# CPU.net
KiCad netlist of a schematic drawn in Altium Designer
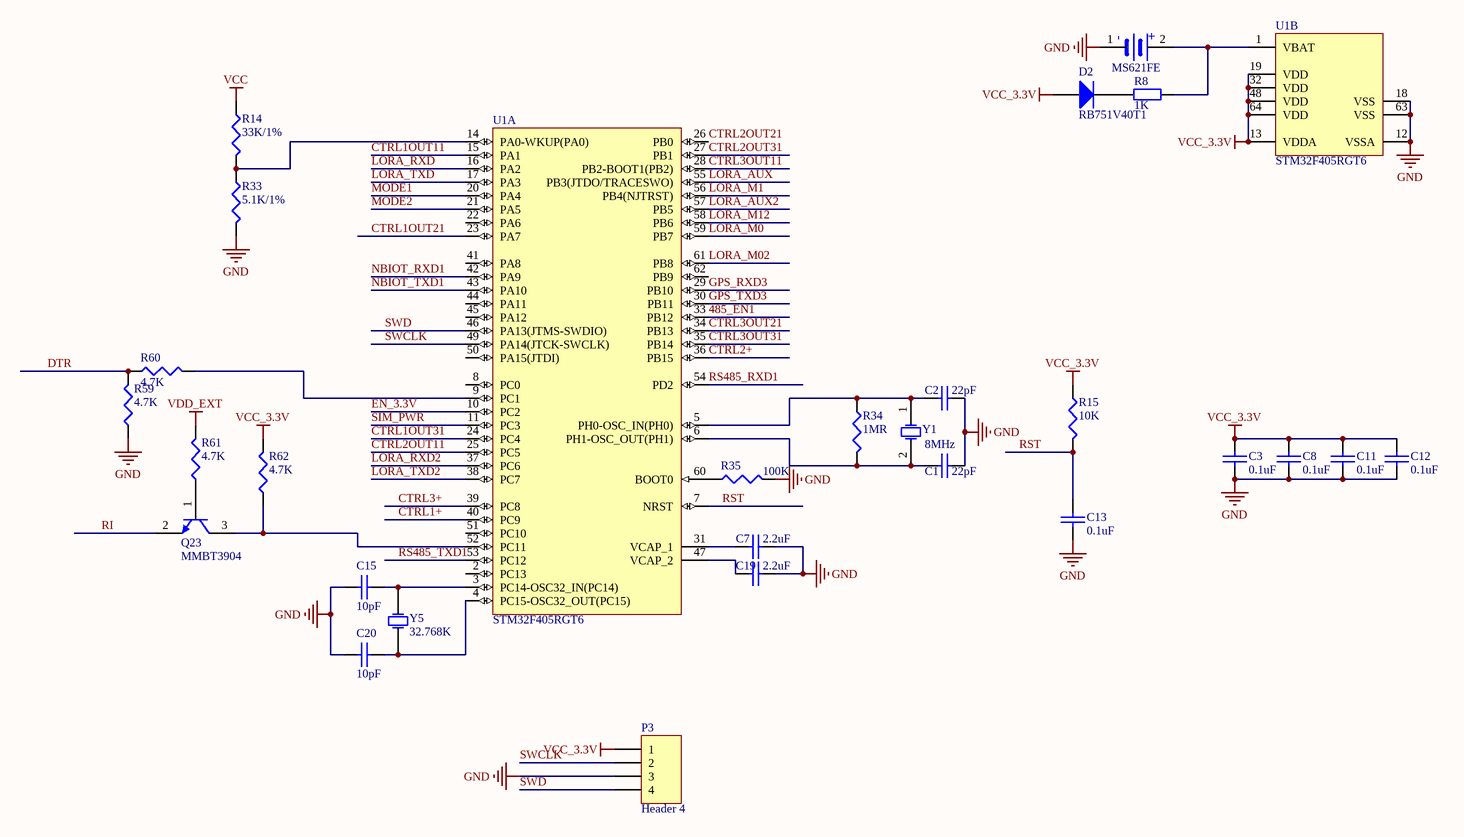
[diagram p0: CPU.SchDoc]

(export (version "E")
  (design (tool "Eeschema 10.0.6"))
  (components
    (comp (ref "C1")
      (value "22pF")
      (footprint "0603c")
      (description "Capacitor")
      (libsource (lib "SM") (part "CAP"))
    )
    (comp (ref "C2")
      (value "22pF")
      (footprint "0603c")
      (description "Capacitor")
      (libsource (lib "SM") (part "CAP"))
    )
    (comp (ref "C3")
      (value "0.1uF")
      (footprint "0603c")
      (description "Capacitor")
      (libsource (lib "SM") (part "CAP"))
    )
    (comp (ref "C7")
      (value "2.2uF")
      (footprint "0603c")
      (description "Capacitor")
      (libsource (lib "SM") (part "CAP"))
    )
    (comp (ref "C8")
      (value "0.1uF")
      (footprint "0603c")
      (description "Capacitor")
      (libsource (lib "SM") (part "CAP"))
    )
    (comp (ref "C11")
      (value "0.1uF")
      (footprint "0603c")
      (description "Capacitor")
      (libsource (lib "SM") (part "CAP"))
    )
    (comp (ref "C12")
      (value "0.1uF")
      (footprint "0603c")
      (description "Capacitor")
      (libsource (lib "SM") (part "CAP"))
    )
    (comp (ref "C13")
      (value "0.1uF")
      (footprint "0603c")
      (description "Capacitor")
      (libsource (lib "SM") (part "CAP"))
    )
    (comp (ref "C15")
      (value "10pF")
      (footprint "0603c")
      (description "Capacitor")
      (libsource (lib "SM") (part "CAP"))
    )
    (comp (ref "C19")
      (value "2.2uF")
      (footprint "0603c")
      (description "Capacitor")
      (libsource (lib "SM") (part "CAP"))
    )
    (comp (ref "C20")
      (value "10pF")
      (footprint "0603c")
      (description "Capacitor")
      (libsource (lib "SM") (part "CAP"))
    )
    (comp (ref "D2")
      (value "RB751V40T1")
      (footprint "SOD323")
      (description "Default Diode")
      (fields (field (name "PUBLISHER") "Altium Limited"))
      (libsource (lib "Miscellaneous Devices") (part "Diode"))
    )
    (comp (ref "MS621FE")
      (value "SBatery")
      (footprint "MS621FE")
      (libsource (lib "Myself_1") (part "SBatery"))
    )
    (comp (ref "P3")
      (value "Header 4")
      (footprint "HDR1X4")
      (description "Header, 4-Pin")
      (fields (field (name "PUBLISHER") "Altium Limited"))
      (libsource (lib "Miscellaneous Connectors") (part "Header 4"))
    )
    (comp (ref "Q23") (value "MMBT3904") (footprint "SOT23-3") (libsource (lib "Schlib1") (part "NPN")))
    (comp (ref "R8")
      (value "1K")
      (footprint "0603R")
      (description "Resistor")
      (fields (field (name "PUBLISHER") "Altium Limited"))
      (libsource (lib "Miscellaneous Devices") (part "Res2"))
    )
    (comp (ref "R14")
      (value "33K/1%")
      (footprint "0603R")
      (description "Resistor")
      (fields (field (name "PUBLISHER") "Altium Limited"))
      (libsource (lib "SM") (part "Res3"))
    )
    (comp (ref "R15")
      (value "10K")
      (footprint "0603R")
      (description "Resistor")
      (fields (field (name "PUBLISHER") "Altium Limited"))
      (libsource (lib "SM") (part "Res3"))
    )
    (comp (ref "R33")
      (value "5.1K/1%")
      (footprint "0603R")
      (description "Resistor")
      (fields (field (name "PUBLISHER") "Altium Limited"))
      (libsource (lib "SM") (part "Res3"))
    )
    (comp (ref "R34")
      (value "1MR")
      (footprint "0603R")
      (description "Resistor")
      (fields (field (name "PUBLISHER") "Altium Limited"))
      (libsource (lib "SM") (part "Res3"))
    )
    (comp (ref "R35")
      (value "100K")
      (footprint "0603R")
      (description "Resistor")
      (fields (field (name "PUBLISHER") "Altium Limited"))
      (libsource (lib "SM") (part "Res3"))
    )
    (comp (ref "R59")
      (value "4.7K")
      (footprint "0603R")
      (libsource (lib "ZWLIntegrated_Library") (part "RES1"))
    )
    (comp (ref "R60")
      (value "4.7K")
      (footprint "0603R")
      (libsource (lib "ZWLIntegrated_Library") (part "RES1"))
    )
    (comp (ref "R61")
      (value "4.7K")
      (footprint "0603R")
      (libsource (lib "ZWLIntegrated_Library") (part "RES1"))
    )
    (comp (ref "R62")
      (value "4.7K")
      (footprint "0603R")
      (libsource (lib "ZWLIntegrated_Library") (part "RES1"))
    )
    (comp (ref "U1")
      (value "STM32F405RGT6")
      (footprint "STM-LQFP64_N")
      (fields (field (name "MANUFACTURER") "STMicroelectronics"))
      (libsource (lib "STMicroelectronics STM32 F4") (part "STM32F405RGT6"))
    )
    (comp (ref "Y1")
      (value "8MHz")
      (footprint "CRAY_5032")
      (description "Crystal Oscillator")
      (fields (field (name "PUBLISHER") "Altium Limited"))
      (libsource (lib "Miscellaneous Devices") (part "XTAL"))
    )
    (comp (ref "Y5")
      (value "32.768K")
      (footprint "32.768K")
      (description "Crystal Oscillator")
      (fields (field (name "PUBLISHER") "Altium Limited"))
      (libsource (lib "") (part "XTAL_1"))
    )
  )
  (nets
    (net (code "1") (name "/485_EN1") (class "Default")
      (node (ref "U1") (pin "33") (pinfunction "PB12_33") (pintype "bidirectional"))
    )
    (net (code "2") (name "/CTRL1+") (class "Default")
      (node (ref "U1") (pin "40") (pinfunction "PC9_40") (pintype "bidirectional"))
    )
    (net (code "3") (name "/CTRL1OUT11") (class "Default")
      (node (ref "U1") (pin "15") (pinfunction "PA1_15") (pintype "bidirectional"))
    )
    (net (code "4") (name "/CTRL1OUT21") (class "Default")
      (node (ref "U1") (pin "23") (pinfunction "PA7_23") (pintype "bidirectional"))
    )
    (net (code "5") (name "/CTRL1OUT31") (class "Default")
      (node (ref "U1") (pin "24") (pinfunction "PC4_24") (pintype "bidirectional"))
    )
    (net (code "6") (name "/CTRL2+") (class "Default")
      (node (ref "U1") (pin "36") (pinfunction "PB15_36") (pintype "bidirectional"))
    )
    (net (code "7") (name "/CTRL2OUT11") (class "Default")
      (node (ref "U1") (pin "25") (pinfunction "PC5_25") (pintype "bidirectional"))
    )
    (net (code "8") (name "/CTRL2OUT21") (class "Default")
      (node (ref "U1") (pin "26") (pinfunction "PB0_26") (pintype "bidirectional"))
    )
    (net (code "9") (name "/CTRL2OUT31") (class "Default")
      (node (ref "U1") (pin "27") (pinfunction "PB1_27") (pintype "bidirectional"))
    )
    (net (code "10") (name "/CTRL3+") (class "Default")
      (node (ref "U1") (pin "39") (pinfunction "PC8_39") (pintype "bidirectional"))
    )
    (net (code "11") (name "/CTRL3OUT11") (class "Default")
      (node (ref "U1") (pin "28") (pinfunction "PB2-BOOT1(PB2)_28") (pintype "bidirectional"))
    )
    (net (code "12") (name "/CTRL3OUT21") (class "Default")
      (node (ref "U1") (pin "34") (pinfunction "PB13_34") (pintype "bidirectional"))
    )
    (net (code "13") (name "/CTRL3OUT31") (class "Default")
      (node (ref "U1") (pin "35") (pinfunction "PB14_35") (pintype "bidirectional"))
    )
    (net (code "14") (name "/DTR") (class "Default")
      (node (ref "R59") (pin "2") (pinfunction "2_2") (pintype "passive"))
      (node (ref "R60") (pin "1") (pinfunction "1_1") (pintype "passive"))
    )
    (net (code "15") (name "/EN_3.3V") (class "Default")
      (node (ref "U1") (pin "10") (pinfunction "PC2_10") (pintype "bidirectional"))
    )
    (net (code "16") (name "/GPS_RXD3") (class "Default")
      (node (ref "U1") (pin "29") (pinfunction "PB10_29") (pintype "bidirectional"))
    )
    (net (code "17") (name "/GPS_TXD3") (class "Default")
      (node (ref "U1") (pin "30") (pinfunction "PB11_30") (pintype "bidirectional"))
    )
    (net (code "18") (name "/LORA_AUX") (class "Default")
      (node (ref "U1") (pin "55") (pinfunction "PB3(JTDO/TRACESWO)_55") (pintype "bidirectional"))
    )
    (net (code "19") (name "/LORA_AUX2") (class "Default")
      (node (ref "U1") (pin "57") (pinfunction "PB5_57") (pintype "bidirectional"))
    )
    (net (code "20") (name "/LORA_M0") (class "Default")
      (node (ref "U1") (pin "59") (pinfunction "PB7_59") (pintype "bidirectional"))
    )
    (net (code "21") (name "/LORA_M1") (class "Default")
      (node (ref "U1") (pin "56") (pinfunction "PB4(NJTRST)_56") (pintype "bidirectional"))
    )
    (net (code "22") (name "/LORA_M02") (class "Default")
      (node (ref "U1") (pin "61") (pinfunction "PB8_61") (pintype "bidirectional"))
    )
    (net (code "23") (name "/LORA_M12") (class "Default")
      (node (ref "U1") (pin "58") (pinfunction "PB6_58") (pintype "bidirectional"))
    )
    (net (code "24") (name "/LORA_RXD") (class "Default")
      (node (ref "U1") (pin "16") (pinfunction "PA2_16") (pintype "bidirectional"))
    )
    (net (code "25") (name "/LORA_RXD2") (class "Default")
      (node (ref "U1") (pin "37") (pinfunction "PC6_37") (pintype "bidirectional"))
    )
    (net (code "26") (name "/LORA_TXD") (class "Default")
      (node (ref "U1") (pin "17") (pinfunction "PA3_17") (pintype "bidirectional"))
    )
    (net (code "27") (name "/LORA_TXD2") (class "Default")
      (node (ref "U1") (pin "38") (pinfunction "PC7_38") (pintype "bidirectional"))
    )
    (net (code "28") (name "/MODE1") (class "Default")
      (node (ref "U1") (pin "20") (pinfunction "PA4_20") (pintype "bidirectional"))
    )
    (net (code "29") (name "/MODE2") (class "Default")
      (node (ref "U1") (pin "21") (pinfunction "PA5_21") (pintype "bidirectional"))
    )
    (net (code "30") (name "/NBIOT_RXD1") (class "Default")
      (node (ref "U1") (pin "42") (pinfunction "PA9_42") (pintype "bidirectional"))
    )
    (net (code "31") (name "/NBIOT_TXD1") (class "Default")
      (node (ref "U1") (pin "43") (pinfunction "PA10_43") (pintype "bidirectional"))
    )
    (net (code "32") (name "/RI") (class "Default")
      (node (ref "Q23") (pin "2") (pinfunction "E_2") (pintype "passive"))
    )
    (net (code "33") (name "/RS485_RXD1") (class "Default")
      (node (ref "U1") (pin "54") (pinfunction "PD2_54") (pintype "bidirectional"))
    )
    (net (code "34") (name "/RS485_TXD1") (class "Default")
      (node (ref "U1") (pin "53") (pinfunction "PC12_53") (pintype "bidirectional"))
    )
    (net (code "35") (name "/RST") (class "Default")
      (node (ref "C13") (pin "2") (pinfunction "2_2") (pintype "passive"))
      (node (ref "R15") (pin "2") (pinfunction "2_2") (pintype "passive"))
      (node (ref "U1") (pin "7") (pinfunction "NRST_7") (pintype "bidirectional"))
    )
    (net (code "36") (name "/SIM_PWR") (class "Default")
      (node (ref "U1") (pin "11") (pinfunction "PC3_11") (pintype "bidirectional"))
    )
    (net (code "37") (name "/SWCLK") (class "Default")
      (node (ref "P3") (pin "2") (pinfunction "2_2") (pintype "passive"))
      (node (ref "U1") (pin "49") (pinfunction "PA14(JTCK-SWCLK)_49") (pintype "bidirectional"))
    )
    (net (code "38") (name "/SWD") (class "Default")
      (node (ref "P3") (pin "4") (pinfunction "4_4") (pintype "passive"))
      (node (ref "U1") (pin "46") (pinfunction "PA13(JTMS-SWDIO)_46") (pintype "bidirectional"))
    )
    (net (code "39") (name "GND") (class "Default")
      (node (ref "C1") (pin "1") (pinfunction "1_1") (pintype "passive"))
      (node (ref "C11") (pin "1") (pinfunction "1_1") (pintype "passive"))
      (node (ref "C12") (pin "1") (pinfunction "1_1") (pintype "passive"))
      (node (ref "C13") (pin "1") (pinfunction "1_1") (pintype "passive"))
      (node (ref "C15") (pin "1") (pinfunction "1_1") (pintype "passive"))
      (node (ref "C19") (pin "1") (pinfunction "1_1") (pintype "passive"))
      (node (ref "C2") (pin "1") (pinfunction "1_1") (pintype "passive"))
      (node (ref "C20") (pin "1") (pinfunction "1_1") (pintype "passive"))
      (node (ref "C3") (pin "1") (pinfunction "1_1") (pintype "passive"))
      (node (ref "C7") (pin "1") (pinfunction "1_1") (pintype "passive"))
      (node (ref "C8") (pin "1") (pinfunction "1_1") (pintype "passive"))
      (node (ref "MS621FE") (pin "1") (pinfunction "1_1") (pintype "passive"))
      (node (ref "P3") (pin "3") (pinfunction "3_3") (pintype "passive"))
      (node (ref "R33") (pin "2") (pinfunction "2_2") (pintype "passive"))
      (node (ref "R35") (pin "2") (pinfunction "2_2") (pintype "passive"))
      (node (ref "R59") (pin "1") (pinfunction "1_1") (pintype "passive"))
      (node (ref "U1") (pin "12") (pinfunction "VSSA_12") (pintype "power_in"))
      (node (ref "U1") (pin "18") (pinfunction "VSS_18") (pintype "power_in"))
      (node (ref "U1") (pin "63") (pinfunction "VSS_63") (pintype "power_in"))
    )
    (net (code "40") (name "Net-(D2-K)") (class "Default")
      (node (ref "D2") (pin "2") (pinfunction "K_2") (pintype "passive"))
      (node (ref "R8") (pin "1") (pinfunction "1_1") (pintype "passive"))
    )
    (net (code "41") (name "Net-(Q23-B)") (class "Default")
      (node (ref "Q23") (pin "1") (pinfunction "B_1") (pintype "passive"))
      (node (ref "R61") (pin "1") (pinfunction "1_1") (pintype "passive"))
    )
    (net (code "42") (name "Net-(Q23-C)") (class "Default")
      (node (ref "Q23") (pin "3") (pinfunction "C_3") (pintype "passive"))
      (node (ref "R62") (pin "1") (pinfunction "1_1") (pintype "passive"))
      (node (ref "U1") (pin "52") (pinfunction "PC11_52") (pintype "bidirectional"))
    )
    (net (code "43") (name "Net-(U1A-BOOT0)") (class "Default")
      (node (ref "R35") (pin "1") (pinfunction "1_1") (pintype "passive"))
      (node (ref "U1") (pin "60") (pinfunction "BOOT0_60") (pintype "input"))
    )
    (net (code "44") (name "Net-(U1A-PA0-WKUP(PA0))") (class "Default")
      (node (ref "R14") (pin "2") (pinfunction "2_2") (pintype "passive"))
      (node (ref "R33") (pin "1") (pinfunction "1_1") (pintype "passive"))
      (node (ref "U1") (pin "14") (pinfunction "PA0-WKUP(PA0)_14") (pintype "bidirectional"))
    )
    (net (code "45") (name "Net-(U1A-PC1)") (class "Default")
      (node (ref "R60") (pin "2") (pinfunction "2_2") (pintype "passive"))
      (node (ref "U1") (pin "9") (pinfunction "PC1_9") (pintype "bidirectional"))
    )
    (net (code "46") (name "Net-(U1A-PC14-OSC32_IN(PC14))") (class "Default")
      (node (ref "C15") (pin "2") (pinfunction "2_2") (pintype "passive"))
      (node (ref "U1") (pin "3") (pinfunction "PC14-OSC32_IN(PC14)_3") (pintype "bidirectional"))
      (node (ref "Y5") (pin "1") (pinfunction "OSC1_1") (pintype "passive"))
    )
    (net (code "47") (name "Net-(U1A-PC15-OSC32_OUT(PC15))") (class "Default")
      (node (ref "C20") (pin "2") (pinfunction "2_2") (pintype "passive"))
      (node (ref "U1") (pin "4") (pinfunction "PC15-OSC32_OUT(PC15)_4") (pintype "bidirectional"))
      (node (ref "Y5") (pin "2") (pinfunction "OSC2_2") (pintype "passive"))
    )
    (net (code "48") (name "Net-(U1A-PH0-OSC_IN(PH0))") (class "Default")
      (node (ref "C2") (pin "2") (pinfunction "2_2") (pintype "passive"))
      (node (ref "R34") (pin "1") (pinfunction "1_1") (pintype "passive"))
      (node (ref "U1") (pin "5") (pinfunction "PH0-OSC_IN(PH0)_5") (pintype "bidirectional"))
      (node (ref "Y1") (pin "1") (pinfunction "OSC1_1") (pintype "passive"))
    )
    (net (code "49") (name "Net-(U1A-PH1-OSC_OUT(PH1))") (class "Default")
      (node (ref "C1") (pin "2") (pinfunction "2_2") (pintype "passive"))
      (node (ref "R34") (pin "2") (pinfunction "2_2") (pintype "passive"))
      (node (ref "U1") (pin "6") (pinfunction "PH1-OSC_OUT(PH1)_6") (pintype "bidirectional"))
      (node (ref "Y1") (pin "2") (pinfunction "OSC2_2") (pintype "passive"))
    )
    (net (code "50") (name "Net-(U1A-VCAP_1)") (class "Default")
      (node (ref "C7") (pin "2") (pinfunction "2_2") (pintype "passive"))
      (node (ref "U1") (pin "31") (pinfunction "VCAP_1_31") (pintype "power_in"))
    )
    (net (code "51") (name "Net-(U1A-VCAP_2)") (class "Default")
      (node (ref "C19") (pin "2") (pinfunction "2_2") (pintype "passive"))
      (node (ref "U1") (pin "47") (pinfunction "VCAP_2_47") (pintype "power_in"))
    )
    (net (code "52") (name "Net-(U1B-VBAT)") (class "Default")
      (node (ref "MS621FE") (pin "2") (pinfunction "2_2") (pintype "passive"))
      (node (ref "R8") (pin "2") (pinfunction "2_2") (pintype "passive"))
      (node (ref "U1") (pin "1") (pinfunction "VBAT_1") (pintype "power_in"))
    )
    (net (code "53") (name "VCC") (class "Default")
      (node (ref "R14") (pin "1") (pinfunction "1_1") (pintype "passive"))
    )
    (net (code "54") (name "VCC_3.3V") (class "Default")
      (node (ref "C11") (pin "2") (pinfunction "2_2") (pintype "passive"))
      (node (ref "C12") (pin "2") (pinfunction "2_2") (pintype "passive"))
      (node (ref "C3") (pin "2") (pinfunction "2_2") (pintype "passive"))
      (node (ref "C8") (pin "2") (pinfunction "2_2") (pintype "passive"))
      (node (ref "D2") (pin "1") (pinfunction "A_1") (pintype "passive"))
      (node (ref "P3") (pin "1") (pinfunction "1_1") (pintype "passive"))
      (node (ref "R15") (pin "1") (pinfunction "1_1") (pintype "passive"))
      (node (ref "R62") (pin "2") (pinfunction "2_2") (pintype "passive"))
      (node (ref "U1") (pin "13") (pinfunction "VDDA_13") (pintype "power_in"))
      (node (ref "U1") (pin "19") (pinfunction "VDD_19") (pintype "power_in"))
      (node (ref "U1") (pin "32") (pinfunction "VDD_32") (pintype "power_in"))
      (node (ref "U1") (pin "48") (pinfunction "VDD_48") (pintype "power_in"))
      (node (ref "U1") (pin "64") (pinfunction "VDD_64") (pintype "power_in"))
    )
    (net (code "55") (name "VDD_EXT") (class "Default")
      (node (ref "R61") (pin "2") (pinfunction "2_2") (pintype "passive"))
    )
    (net (code "56") (name "unconnected-(U1A-PA6-Pad22)") (class "Default")
      (node (ref "U1") (pin "22") (pinfunction "PA6_22") (pintype "bidirectional"))
    )
    (net (code "57") (name "unconnected-(U1A-PA8-Pad41)") (class "Default")
      (node (ref "U1") (pin "41") (pinfunction "PA8_41") (pintype "bidirectional"))
    )
    (net (code "58") (name "unconnected-(U1A-PA11-Pad44)") (class "Default")
      (node (ref "U1") (pin "44") (pinfunction "PA11_44") (pintype "bidirectional"))
    )
    (net (code "59") (name "unconnected-(U1A-PA12-Pad45)") (class "Default")
      (node (ref "U1") (pin "45") (pinfunction "PA12_45") (pintype "bidirectional"))
    )
    (net (code "60") (name "unconnected-(U1A-PA15(JTDI)-Pad50)") (class "Default")
      (node (ref "U1") (pin "50") (pinfunction "PA15(JTDI)_50") (pintype "bidirectional"))
    )
    (net (code "61") (name "unconnected-(U1A-PB9-Pad62)") (class "Default")
      (node (ref "U1") (pin "62") (pinfunction "PB9_62") (pintype "bidirectional"))
    )
    (net (code "62") (name "unconnected-(U1A-PC0-Pad8)") (class "Default")
      (node (ref "U1") (pin "8") (pinfunction "PC0_8") (pintype "bidirectional"))
    )
    (net (code "63") (name "unconnected-(U1A-PC10-Pad51)") (class "Default")
      (node (ref "U1") (pin "51") (pinfunction "PC10_51") (pintype "bidirectional"))
    )
    (net (code "64") (name "unconnected-(U1A-PC13-Pad2)") (class "Default")
      (node (ref "U1") (pin "2") (pinfunction "PC13_2") (pintype "bidirectional"))
    )
  )
)
